# Uncertainty_Device.net
KiCad netlist of a schematic drawn in EAGLE
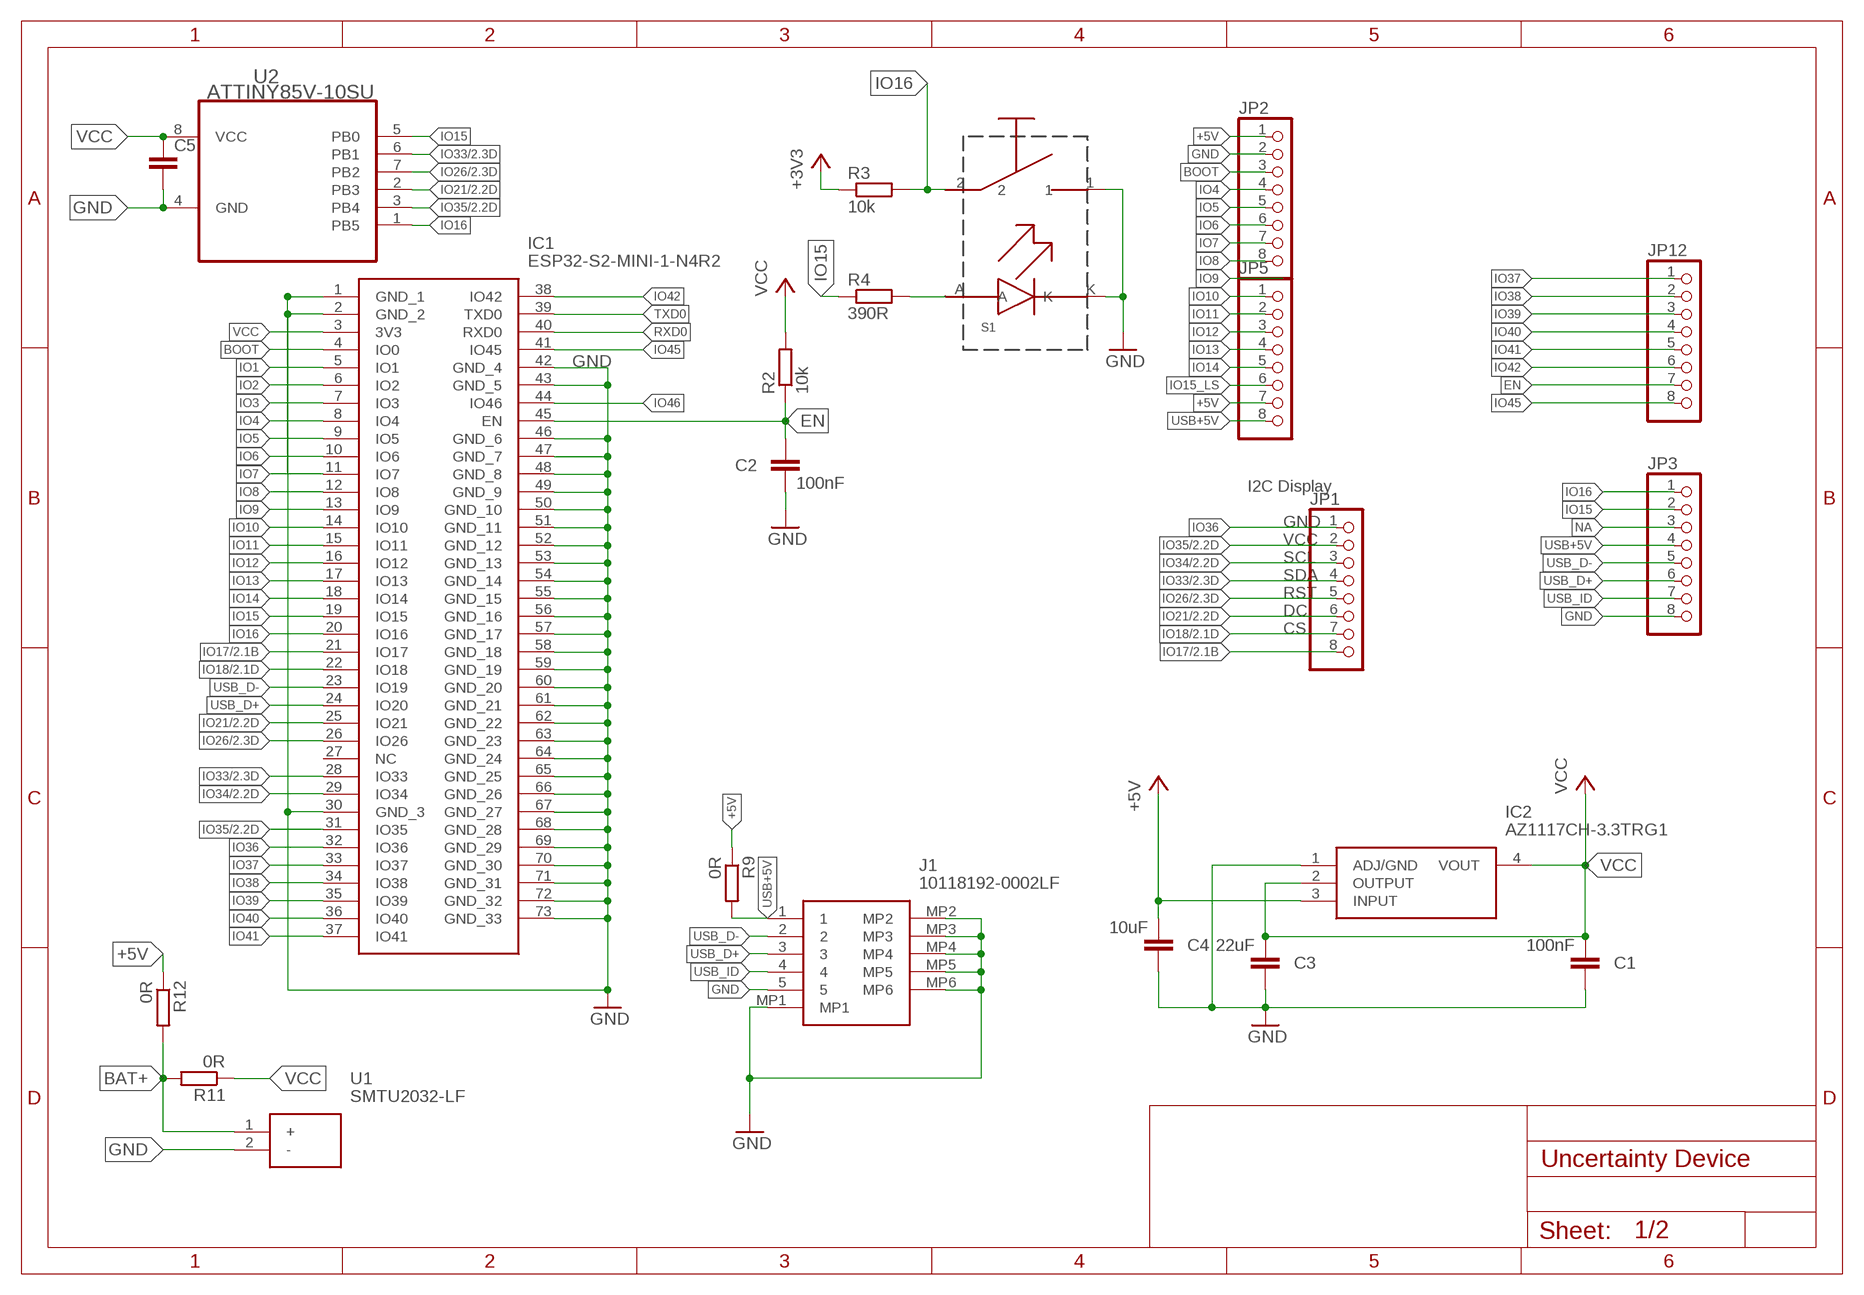
[diagram p0: schematic, sheet 1]
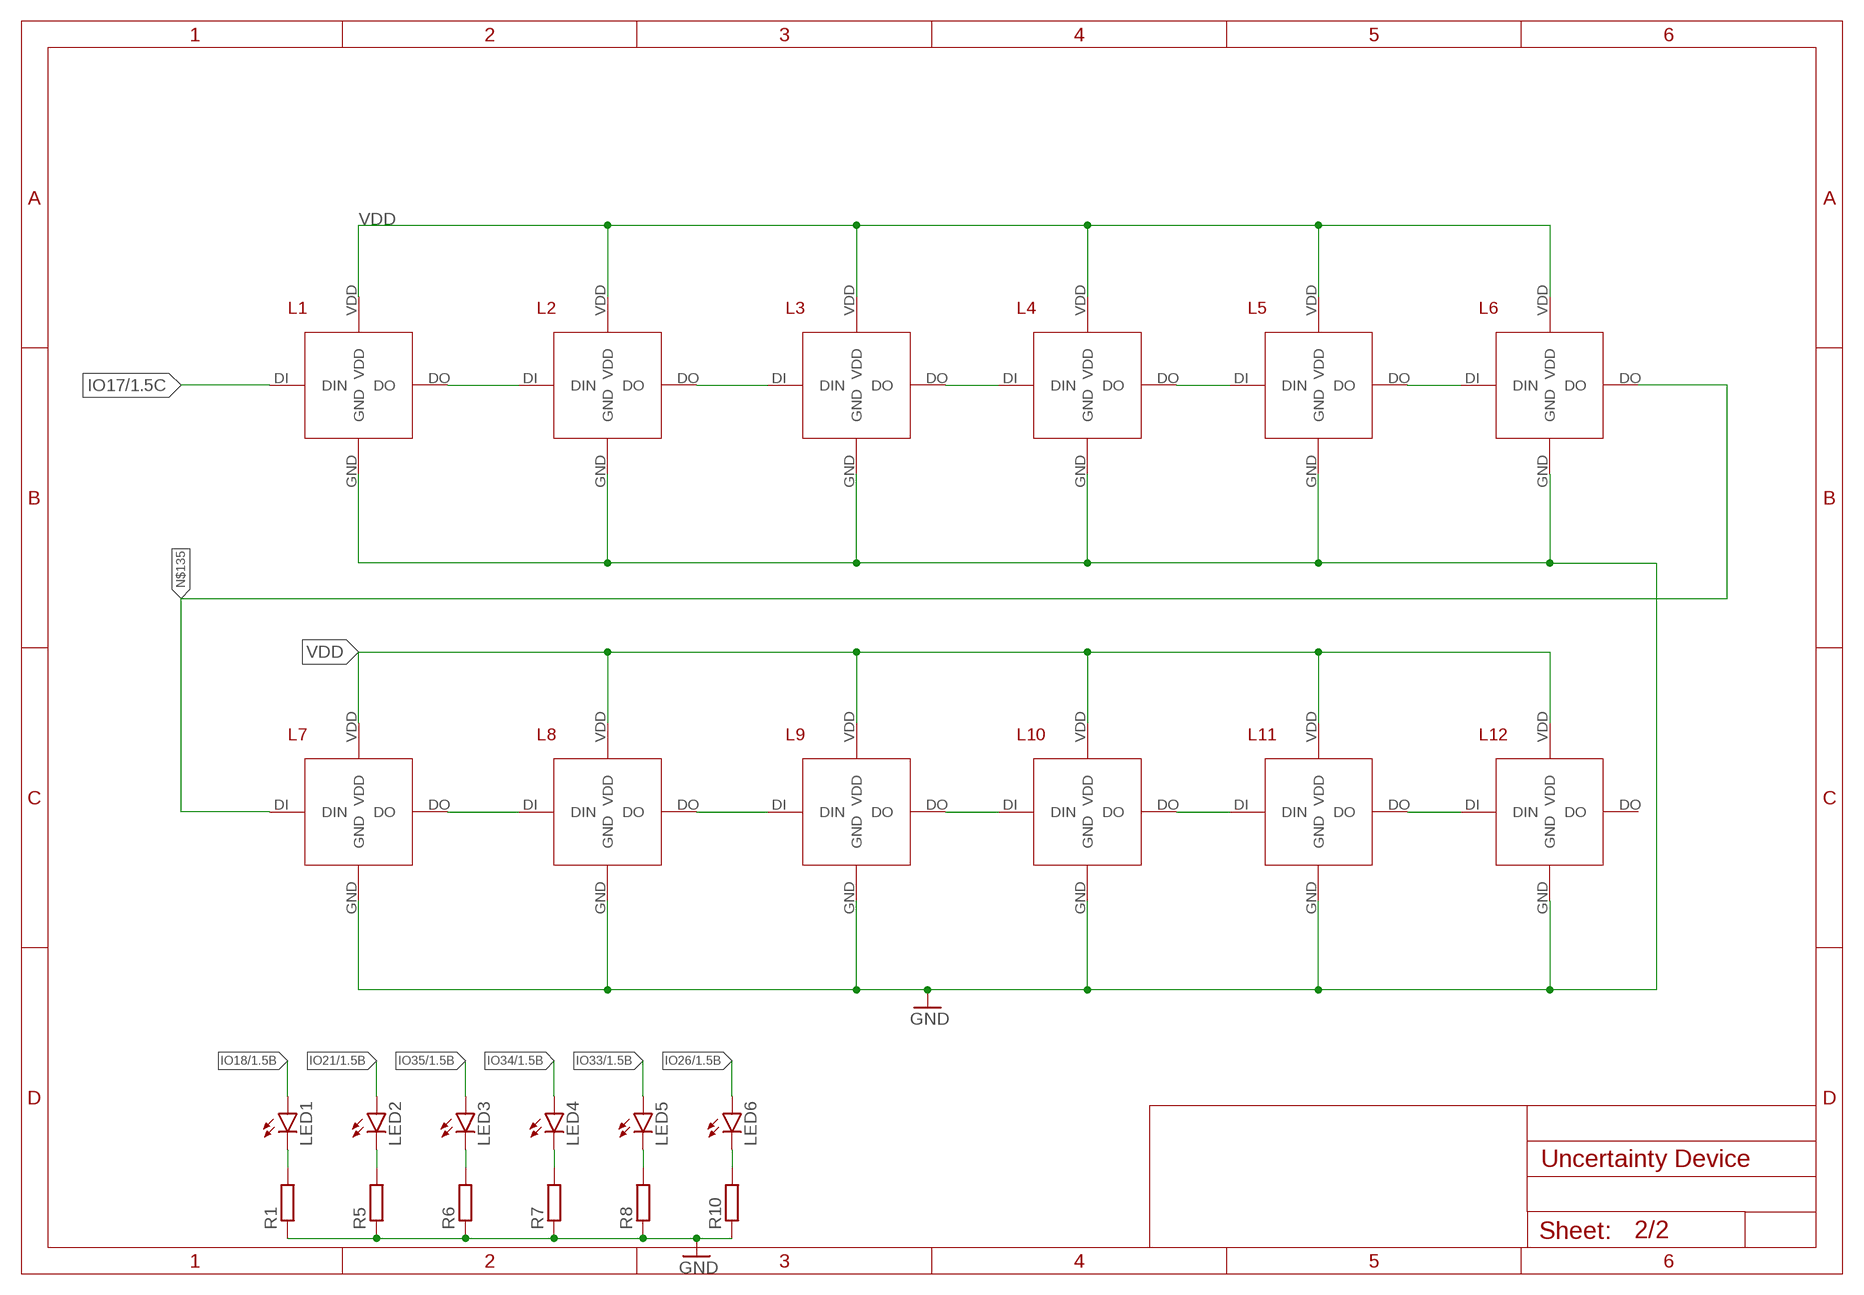
[diagram p1: schematic, sheet 2]

(export (version "E")
  (design (tool "Eeschema 10.0.6"))
  (components
    (comp (ref "C1")
      (value "100nF")
      (footprint "eagle-import:C0805")
      (libsource (lib "eagle-import") (part "C-EUC0805"))
    )
    (comp (ref "C2")
      (value "100nF")
      (footprint "eagle-import:C0805")
      (libsource (lib "eagle-import") (part "C-EUC0805"))
    )
    (comp (ref "C3")
      (value "22uF")
      (footprint "eagle-import:C0805")
      (libsource (lib "eagle-import") (part "C-EUC0805"))
    )
    (comp (ref "C4")
      (value "10uF")
      (footprint "eagle-import:C0805")
      (libsource (lib "eagle-import") (part "C-EUC0805"))
    )
    (comp (ref "C5")
      (value "C-EUC0805")
      (footprint "eagle-import:C0805")
      (libsource (lib "eagle-import") (part "resistor_C-EUC0805"))
    )
    (comp (ref "IC1")
      (value "ESP32-S2-MINI-1-N4R2")
      (footprint "eagle-import:ESP32S2MINI1N4R2")
      (fields (field (name "MOUSER_PART_NUMBER") "356-ESP32S2MINI1N4R2"))
      (libsource (lib "eagle-import") (part "ESP32-S2-MINI-1-N4R2"))
    )
    (comp (ref "IC2")
      (value "AZ1117CH-3.3TRG1")
      (footprint "eagle-import:SOT230P700X180-4N")
      (fields (field (name "MOUSER_PART_NUMBER") "621-AZ1117CH-3.3TRG1"))
      (libsource (lib "eagle-import") (part "AZ1117CH-3.3TRG1"))
    )
    (comp (ref "J1")
      (value "10118192-0002LF")
      (footprint "eagle-import:101181920002LF")
      (libsource (lib "eagle-import") (part "10118192-0002LF"))
    )
    (comp (ref "JP1")
      (value "PINHD-1X8")
      (footprint "eagle-import:1X08")
      (libsource (lib "eagle-import") (part "PINHD-1X8"))
    )
    (comp (ref "JP2")
      (value "PINHD-1X8")
      (footprint "eagle-import:1X08")
      (libsource (lib "eagle-import") (part "PINHD-1X8"))
    )
    (comp (ref "JP3")
      (value "PINHD-1X8")
      (footprint "eagle-import:1X08")
      (libsource (lib "eagle-import") (part "PINHD-1X8"))
    )
    (comp (ref "JP5")
      (value "PINHD-1X8")
      (footprint "eagle-import:1X08")
      (libsource (lib "eagle-import") (part "PINHD-1X8"))
    )
    (comp (ref "JP12")
      (value "PINHD-1X8")
      (footprint "eagle-import:1X08")
      (libsource (lib "eagle-import") (part "PINHD-1X8"))
    )
    (comp (ref "R2")
      (value "10k")
      (footprint "eagle-import:R0805")
      (libsource (lib "eagle-import") (part "R-EU_R0805"))
    )
    (comp (ref "R3")
      (value "10k")
      (footprint "eagle-import:R0805")
      (libsource (lib "eagle-import") (part "R-EU_R0805"))
    )
    (comp (ref "R4")
      (value "390R")
      (footprint "eagle-import:R0805")
      (libsource (lib "eagle-import") (part "R-EU_R0805"))
    )
    (comp (ref "R9")
      (value "0R")
      (footprint "eagle-import:R0805")
      (libsource (lib "eagle-import") (part "R-EU_R0805"))
    )
    (comp (ref "R11")
      (value "0R")
      (footprint "eagle-import:R0805")
      (libsource (lib "eagle-import") (part "R-EU_R0805"))
    )
    (comp (ref "R12")
      (value "0R")
      (footprint "eagle-import:R0805")
      (libsource (lib "eagle-import") (part "R-EU_R0805"))
    )
    (comp (ref "S1")
      (value "3006SMD")
      (footprint "eagle-import:SMD")
      (libsource (lib "eagle-import") (part "3006SMD"))
    )
    (comp (ref "U1")
      (value "SMTU2032-LF")
      (footprint "eagle-import:SMTU2032LF")
      (fields (field (name "MOUSER_PART_NUMBER") "614-SMTU2032-LF"))
      (libsource (lib "eagle-import") (part "SMTU2032-LF"))
    )
    (comp (ref "U2")
      (value "ATTINY85V-10SU")
      (footprint "eagle-import:SOIC127P798X216-8N")
      (libsource (lib "eagle-import") (part "ATTINY85V-10SU"))
    )
    (comp (ref "L1")
      (value "XL-1615RGBC")
      (footprint "eagle-import:XL-1615RGBC-WS2812")
      (libsource (lib "eagle-import") (part "XL-1615RGBC"))
    )
    (comp (ref "L2")
      (value "XL-1615RGBC")
      (footprint "eagle-import:XL-1615RGBC-WS2812")
      (libsource (lib "eagle-import") (part "XL-1615RGBC"))
    )
    (comp (ref "L3")
      (value "XL-1615RGBC")
      (footprint "eagle-import:XL-1615RGBC-WS2812")
      (libsource (lib "eagle-import") (part "XL-1615RGBC"))
    )
    (comp (ref "L4")
      (value "XL-1615RGBC")
      (footprint "eagle-import:XL-1615RGBC-WS2812")
      (libsource (lib "eagle-import") (part "XL-1615RGBC"))
    )
    (comp (ref "L5")
      (value "XL-1615RGBC")
      (footprint "eagle-import:XL-1615RGBC-WS2812")
      (libsource (lib "eagle-import") (part "XL-1615RGBC"))
    )
    (comp (ref "L6")
      (value "XL-1615RGBC")
      (footprint "eagle-import:XL-1615RGBC-WS2812")
      (libsource (lib "eagle-import") (part "XL-1615RGBC"))
    )
    (comp (ref "L7")
      (value "XL-1615RGBC")
      (footprint "eagle-import:XL-1615RGBC-WS2812")
      (libsource (lib "eagle-import") (part "XL-1615RGBC"))
    )
    (comp (ref "L8")
      (value "XL-1615RGBC")
      (footprint "eagle-import:XL-1615RGBC-WS2812")
      (libsource (lib "eagle-import") (part "XL-1615RGBC"))
    )
    (comp (ref "L9")
      (value "XL-1615RGBC")
      (footprint "eagle-import:XL-1615RGBC-WS2812")
      (libsource (lib "eagle-import") (part "XL-1615RGBC"))
    )
    (comp (ref "L10")
      (value "XL-1615RGBC")
      (footprint "eagle-import:XL-1615RGBC-WS2812")
      (libsource (lib "eagle-import") (part "XL-1615RGBC"))
    )
    (comp (ref "L11")
      (value "XL-1615RGBC")
      (footprint "eagle-import:XL-1615RGBC-WS2812")
      (libsource (lib "eagle-import") (part "XL-1615RGBC"))
    )
    (comp (ref "L12")
      (value "XL-1615RGBC")
      (footprint "eagle-import:XL-1615RGBC-WS2812")
      (libsource (lib "eagle-import") (part "XL-1615RGBC"))
    )
    (comp (ref "LED1")
      (value "LEDCHIPLED_0805")
      (footprint "eagle-import:CHIPLED_0805")
      (libsource (lib "eagle-import") (part "LEDCHIPLED_0805"))
    )
    (comp (ref "LED2")
      (value "LEDCHIPLED_0805")
      (footprint "eagle-import:CHIPLED_0805")
      (libsource (lib "eagle-import") (part "LEDCHIPLED_0805"))
    )
    (comp (ref "LED3")
      (value "LEDCHIPLED_0805")
      (footprint "eagle-import:CHIPLED_0805")
      (libsource (lib "eagle-import") (part "LEDCHIPLED_0805"))
    )
    (comp (ref "LED4")
      (value "LEDCHIPLED_0805")
      (footprint "eagle-import:CHIPLED_0805")
      (libsource (lib "eagle-import") (part "LEDCHIPLED_0805"))
    )
    (comp (ref "LED5")
      (value "LEDCHIPLED_0805")
      (footprint "eagle-import:CHIPLED_0805")
      (libsource (lib "eagle-import") (part "LEDCHIPLED_0805"))
    )
    (comp (ref "LED6")
      (value "LEDCHIPLED_0805")
      (footprint "eagle-import:CHIPLED_0805")
      (libsource (lib "eagle-import") (part "LEDCHIPLED_0805"))
    )
    (comp (ref "R1")
      (value "R-EU_R0805")
      (footprint "eagle-import:R0805")
      (libsource (lib "eagle-import") (part "R-EU_R0805"))
    )
    (comp (ref "R5")
      (value "R-EU_R0805")
      (footprint "eagle-import:R0805")
      (libsource (lib "eagle-import") (part "R-EU_R0805"))
    )
    (comp (ref "R6")
      (value "R-EU_R0805")
      (footprint "eagle-import:R0805")
      (libsource (lib "eagle-import") (part "R-EU_R0805"))
    )
    (comp (ref "R7")
      (value "R-EU_R0805")
      (footprint "eagle-import:R0805")
      (libsource (lib "eagle-import") (part "R-EU_R0805"))
    )
    (comp (ref "R8")
      (value "R-EU_R0805")
      (footprint "eagle-import:R0805")
      (libsource (lib "eagle-import") (part "R-EU_R0805"))
    )
    (comp (ref "R10")
      (value "R-EU_R0805")
      (footprint "eagle-import:R0805")
      (libsource (lib "eagle-import") (part "R-EU_R0805"))
    )
  )
  (nets
    (net (code "1") (name "+3V3") (class "Default")
      (node (ref "R3") (pin "1") (pinfunction "1_1") (pintype "passive"))
    )
    (net (code "2") (name "+5V") (class "Default")
      (node (ref "C4") (pin "2") (pinfunction "2_2") (pintype "passive"))
      (node (ref "IC2") (pin "3") (pinfunction "INPUT_3") (pintype "bidirectional"))
      (node (ref "JP2") (pin "1") (pinfunction "1_1") (pintype "passive"))
      (node (ref "JP5") (pin "7") (pinfunction "7_7") (pintype "passive"))
      (node (ref "R12") (pin "1") (pinfunction "1_1") (pintype "passive"))
      (node (ref "R9") (pin "1") (pinfunction "1_1") (pintype "passive"))
    )
    (net (code "3") (name "BAT+") (class "Default")
      (node (ref "R11") (pin "2") (pinfunction "2_2") (pintype "passive"))
      (node (ref "R12") (pin "2") (pinfunction "2_2") (pintype "passive"))
      (node (ref "U1") (pin "1") (pinfunction "+_1") (pintype "bidirectional"))
    )
    (net (code "4") (name "BOOT") (class "Default")
      (node (ref "IC1") (pin "4") (pinfunction "IO0_4") (pintype "bidirectional"))
      (node (ref "JP2") (pin "3") (pinfunction "3_3") (pintype "passive"))
    )
    (net (code "5") (name "EN") (class "Default")
      (node (ref "C2") (pin "1") (pinfunction "1_1") (pintype "passive"))
      (node (ref "IC1") (pin "45") (pinfunction "EN_45") (pintype "bidirectional"))
      (node (ref "JP12") (pin "7") (pinfunction "7_7") (pintype "passive"))
      (node (ref "R2") (pin "1") (pinfunction "1_1") (pintype "passive"))
    )
    (net (code "6") (name "GND") (class "Default")
      (node (ref "C1") (pin "1") (pinfunction "1_1") (pintype "passive"))
      (node (ref "C2") (pin "2") (pinfunction "2_2") (pintype "passive"))
      (node (ref "C3") (pin "1") (pinfunction "1_1") (pintype "passive"))
      (node (ref "C4") (pin "1") (pinfunction "1_1") (pintype "passive"))
      (node (ref "C5") (pin "2") (pinfunction "2_2") (pintype "passive"))
      (node (ref "IC1") (pin "1") (pinfunction "GND_1_1") (pintype "bidirectional"))
      (node (ref "IC1") (pin "2") (pinfunction "GND_2_2") (pintype "bidirectional"))
      (node (ref "IC1") (pin "30") (pinfunction "GND_3_30") (pintype "bidirectional"))
      (node (ref "IC1") (pin "42") (pinfunction "GND_4_42") (pintype "bidirectional"))
      (node (ref "IC1") (pin "43") (pinfunction "GND_5_43") (pintype "bidirectional"))
      (node (ref "IC1") (pin "46") (pinfunction "GND_6_46") (pintype "bidirectional"))
      (node (ref "IC1") (pin "47") (pinfunction "GND_7_47") (pintype "bidirectional"))
      (node (ref "IC1") (pin "48") (pinfunction "GND_8_48") (pintype "bidirectional"))
      (node (ref "IC1") (pin "49") (pinfunction "GND_9_49") (pintype "bidirectional"))
      (node (ref "IC1") (pin "50") (pinfunction "GND_10_50") (pintype "bidirectional"))
      (node (ref "IC1") (pin "51") (pinfunction "GND_11_51") (pintype "bidirectional"))
      (node (ref "IC1") (pin "52") (pinfunction "GND_12_52") (pintype "bidirectional"))
      (node (ref "IC1") (pin "53") (pinfunction "GND_13_53") (pintype "bidirectional"))
      (node (ref "IC1") (pin "54") (pinfunction "GND_14_54") (pintype "bidirectional"))
      (node (ref "IC1") (pin "55") (pinfunction "GND_15_55") (pintype "bidirectional"))
      (node (ref "IC1") (pin "56") (pinfunction "GND_16_56") (pintype "bidirectional"))
      (node (ref "IC1") (pin "57") (pinfunction "GND_17_57") (pintype "bidirectional"))
      (node (ref "IC1") (pin "58") (pinfunction "GND_18_58") (pintype "bidirectional"))
      (node (ref "IC1") (pin "59") (pinfunction "GND_19_59") (pintype "bidirectional"))
      (node (ref "IC1") (pin "60") (pinfunction "GND_20_60") (pintype "bidirectional"))
      (node (ref "IC1") (pin "61") (pinfunction "GND_21_61") (pintype "bidirectional"))
      (node (ref "IC1") (pin "62") (pinfunction "GND_22_62") (pintype "bidirectional"))
      (node (ref "IC1") (pin "63") (pinfunction "GND_23_63") (pintype "bidirectional"))
      (node (ref "IC1") (pin "64") (pinfunction "GND_24_64") (pintype "bidirectional"))
      (node (ref "IC1") (pin "65") (pinfunction "GND_25_65") (pintype "bidirectional"))
      (node (ref "IC1") (pin "66") (pinfunction "GND_26_66") (pintype "bidirectional"))
      (node (ref "IC1") (pin "67") (pinfunction "GND_27_67") (pintype "bidirectional"))
      (node (ref "IC1") (pin "68") (pinfunction "GND_28_68") (pintype "bidirectional"))
      (node (ref "IC1") (pin "69") (pinfunction "GND_29_69") (pintype "bidirectional"))
      (node (ref "IC1") (pin "70") (pinfunction "GND_30_70") (pintype "bidirectional"))
      (node (ref "IC1") (pin "71") (pinfunction "GND_31_71") (pintype "bidirectional"))
      (node (ref "IC1") (pin "72") (pinfunction "GND_32_72") (pintype "bidirectional"))
      (node (ref "IC1") (pin "73") (pinfunction "GND_33_73") (pintype "bidirectional"))
      (node (ref "IC2") (pin "1") (pinfunction "ADJ/GND_1") (pintype "bidirectional"))
      (node (ref "J1") (pin "5") (pinfunction "5_5") (pintype "bidirectional"))
      (node (ref "J1") (pin "MP1") (pinfunction "MP1_MP1") (pintype "bidirectional"))
      (node (ref "J1") (pin "MP2") (pinfunction "MP2_MP2") (pintype "bidirectional"))
      (node (ref "J1") (pin "MP3") (pinfunction "MP3_MP3") (pintype "bidirectional"))
      (node (ref "J1") (pin "MP4") (pinfunction "MP4_MP4") (pintype "bidirectional"))
      (node (ref "J1") (pin "MP5") (pinfunction "MP5_MP5") (pintype "bidirectional"))
      (node (ref "J1") (pin "MP6") (pinfunction "MP6_MP6") (pintype "bidirectional"))
      (node (ref "JP2") (pin "2") (pinfunction "2_2") (pintype "passive"))
      (node (ref "JP3") (pin "8") (pinfunction "8_8") (pintype "passive"))
      (node (ref "L1") (pin "GND") (pinfunction "GND_GND") (pintype "bidirectional"))
      (node (ref "L10") (pin "GND") (pinfunction "GND_GND") (pintype "bidirectional"))
      (node (ref "L11") (pin "GND") (pinfunction "GND_GND") (pintype "bidirectional"))
      (node (ref "L12") (pin "GND") (pinfunction "GND_GND") (pintype "bidirectional"))
      (node (ref "L2") (pin "GND") (pinfunction "GND_GND") (pintype "bidirectional"))
      (node (ref "L3") (pin "GND") (pinfunction "GND_GND") (pintype "bidirectional"))
      (node (ref "L4") (pin "GND") (pinfunction "GND_GND") (pintype "bidirectional"))
      (node (ref "L5") (pin "GND") (pinfunction "GND_GND") (pintype "bidirectional"))
      (node (ref "L6") (pin "GND") (pinfunction "GND_GND") (pintype "bidirectional"))
      (node (ref "L7") (pin "GND") (pinfunction "GND_GND") (pintype "bidirectional"))
      (node (ref "L8") (pin "GND") (pinfunction "GND_GND") (pintype "bidirectional"))
      (node (ref "L9") (pin "GND") (pinfunction "GND_GND") (pintype "bidirectional"))
      (node (ref "R1") (pin "1") (pinfunction "1_1") (pintype "passive"))
      (node (ref "R10") (pin "1") (pinfunction "1_1") (pintype "passive"))
      (node (ref "R5") (pin "1") (pinfunction "1_1") (pintype "passive"))
      (node (ref "R6") (pin "1") (pinfunction "1_1") (pintype "passive"))
      (node (ref "R7") (pin "1") (pinfunction "1_1") (pintype "passive"))
      (node (ref "R8") (pin "1") (pinfunction "1_1") (pintype "passive"))
      (node (ref "S1") (pin "1") (pinfunction "1_1") (pintype "bidirectional"))
      (node (ref "S1") (pin "K") (pinfunction "K_K") (pintype "bidirectional"))
      (node (ref "U1") (pin "2") (pinfunction "-_2") (pintype "bidirectional"))
      (node (ref "U2") (pin "4") (pinfunction "GND_4") (pintype "passive"))
    )
    (net (code "7") (name "IO1") (class "Default")
      (node (ref "IC1") (pin "5") (pinfunction "IO1_5") (pintype "bidirectional"))
    )
    (net (code "8") (name "IO2") (class "Default")
      (node (ref "IC1") (pin "6") (pinfunction "IO2_6") (pintype "bidirectional"))
    )
    (net (code "9") (name "IO3") (class "Default")
      (node (ref "IC1") (pin "7") (pinfunction "IO3_7") (pintype "bidirectional"))
    )
    (net (code "10") (name "IO4") (class "Default")
      (node (ref "IC1") (pin "8") (pinfunction "IO4_8") (pintype "bidirectional"))
      (node (ref "JP2") (pin "4") (pinfunction "4_4") (pintype "passive"))
    )
    (net (code "11") (name "IO5") (class "Default")
      (node (ref "IC1") (pin "9") (pinfunction "IO5_9") (pintype "bidirectional"))
      (node (ref "JP2") (pin "5") (pinfunction "5_5") (pintype "passive"))
    )
    (net (code "12") (name "IO6") (class "Default")
      (node (ref "IC1") (pin "10") (pinfunction "IO6_10") (pintype "bidirectional"))
      (node (ref "JP2") (pin "6") (pinfunction "6_6") (pintype "passive"))
    )
    (net (code "13") (name "IO7") (class "Default")
      (node (ref "IC1") (pin "11") (pinfunction "IO7_11") (pintype "bidirectional"))
      (node (ref "JP2") (pin "7") (pinfunction "7_7") (pintype "passive"))
    )
    (net (code "14") (name "IO8") (class "Default")
      (node (ref "IC1") (pin "12") (pinfunction "IO8_12") (pintype "bidirectional"))
      (node (ref "JP2") (pin "8") (pinfunction "8_8") (pintype "passive"))
    )
    (net (code "15") (name "IO9") (class "Default")
      (node (ref "IC1") (pin "13") (pinfunction "IO9_13") (pintype "bidirectional"))
    )
    (net (code "16") (name "IO10") (class "Default")
      (node (ref "IC1") (pin "14") (pinfunction "IO10_14") (pintype "bidirectional"))
      (node (ref "JP5") (pin "1") (pinfunction "1_1") (pintype "passive"))
    )
    (net (code "17") (name "IO11") (class "Default")
      (node (ref "IC1") (pin "15") (pinfunction "IO11_15") (pintype "bidirectional"))
      (node (ref "JP5") (pin "2") (pinfunction "2_2") (pintype "passive"))
    )
    (net (code "18") (name "IO12") (class "Default")
      (node (ref "IC1") (pin "16") (pinfunction "IO12_16") (pintype "bidirectional"))
      (node (ref "JP5") (pin "3") (pinfunction "3_3") (pintype "passive"))
    )
    (net (code "19") (name "IO13") (class "Default")
      (node (ref "IC1") (pin "17") (pinfunction "IO13_17") (pintype "bidirectional"))
      (node (ref "JP5") (pin "4") (pinfunction "4_4") (pintype "passive"))
    )
    (net (code "20") (name "IO14") (class "Default")
      (node (ref "IC1") (pin "18") (pinfunction "IO14_18") (pintype "bidirectional"))
      (node (ref "JP5") (pin "5") (pinfunction "5_5") (pintype "passive"))
    )
    (net (code "21") (name "IO15") (class "Default")
      (node (ref "IC1") (pin "19") (pinfunction "IO15_19") (pintype "bidirectional"))
      (node (ref "JP3") (pin "2") (pinfunction "2_2") (pintype "passive"))
      (node (ref "R4") (pin "1") (pinfunction "1_1") (pintype "passive"))
      (node (ref "U2") (pin "5") (pinfunction "PB0_5") (pintype "bidirectional"))
    )
    (net (code "22") (name "IO15_LS") (class "Default")
      (node (ref "JP5") (pin "6") (pinfunction "6_6") (pintype "passive"))
    )
    (net (code "23") (name "IO16") (class "Default")
      (node (ref "IC1") (pin "20") (pinfunction "IO16_20") (pintype "bidirectional"))
      (node (ref "JP3") (pin "1") (pinfunction "1_1") (pintype "passive"))
      (node (ref "R3") (pin "2") (pinfunction "2_2") (pintype "passive"))
      (node (ref "S1") (pin "2") (pinfunction "2_2") (pintype "bidirectional"))
      (node (ref "U2") (pin "1") (pinfunction "PB5_1") (pintype "bidirectional"))
    )
    (net (code "24") (name "IO17") (class "Default")
      (node (ref "IC1") (pin "21") (pinfunction "IO17_21") (pintype "bidirectional"))
      (node (ref "JP1") (pin "8") (pinfunction "8_8") (pintype "passive"))
      (node (ref "L1") (pin "DI") (pinfunction "DIN_DI") (pintype "bidirectional"))
    )
    (net (code "25") (name "IO18") (class "Default")
      (node (ref "IC1") (pin "22") (pinfunction "IO18_22") (pintype "bidirectional"))
      (node (ref "JP1") (pin "7") (pinfunction "7_7") (pintype "passive"))
      (node (ref "LED1") (pin "A") (pinfunction "A_A") (pintype "passive"))
    )
    (net (code "26") (name "IO21") (class "Default")
      (node (ref "IC1") (pin "25") (pinfunction "IO21_25") (pintype "bidirectional"))
      (node (ref "JP1") (pin "6") (pinfunction "6_6") (pintype "passive"))
      (node (ref "LED2") (pin "A") (pinfunction "A_A") (pintype "passive"))
      (node (ref "U2") (pin "2") (pinfunction "PB3_2") (pintype "bidirectional"))
    )
    (net (code "27") (name "IO26") (class "Default")
      (node (ref "IC1") (pin "26") (pinfunction "IO26_26") (pintype "bidirectional"))
      (node (ref "JP1") (pin "5") (pinfunction "5_5") (pintype "passive"))
      (node (ref "LED6") (pin "A") (pinfunction "A_A") (pintype "passive"))
      (node (ref "U2") (pin "7") (pinfunction "PB2_7") (pintype "bidirectional"))
    )
    (net (code "28") (name "IO33") (class "Default")
      (node (ref "IC1") (pin "28") (pinfunction "IO33_28") (pintype "bidirectional"))
      (node (ref "JP1") (pin "4") (pinfunction "4_4") (pintype "passive"))
      (node (ref "LED5") (pin "A") (pinfunction "A_A") (pintype "passive"))
      (node (ref "U2") (pin "6") (pinfunction "PB1_6") (pintype "bidirectional"))
    )
    (net (code "29") (name "IO34") (class "Default")
      (node (ref "IC1") (pin "29") (pinfunction "IO34_29") (pintype "bidirectional"))
      (node (ref "JP1") (pin "3") (pinfunction "3_3") (pintype "passive"))
      (node (ref "LED4") (pin "A") (pinfunction "A_A") (pintype "passive"))
    )
    (net (code "30") (name "IO35") (class "Default")
      (node (ref "IC1") (pin "31") (pinfunction "IO35_31") (pintype "bidirectional"))
      (node (ref "JP1") (pin "2") (pinfunction "2_2") (pintype "passive"))
      (node (ref "LED3") (pin "A") (pinfunction "A_A") (pintype "passive"))
      (node (ref "U2") (pin "3") (pinfunction "PB4_3") (pintype "bidirectional"))
    )
    (net (code "31") (name "IO36") (class "Default")
      (node (ref "IC1") (pin "32") (pinfunction "IO36_32") (pintype "bidirectional"))
      (node (ref "JP1") (pin "1") (pinfunction "1_1") (pintype "passive"))
    )
    (net (code "32") (name "IO37") (class "Default")
      (node (ref "IC1") (pin "33") (pinfunction "IO37_33") (pintype "bidirectional"))
      (node (ref "JP12") (pin "1") (pinfunction "1_1") (pintype "passive"))
    )
    (net (code "33") (name "IO38") (class "Default")
      (node (ref "IC1") (pin "34") (pinfunction "IO38_34") (pintype "bidirectional"))
      (node (ref "JP12") (pin "2") (pinfunction "2_2") (pintype "passive"))
    )
    (net (code "34") (name "IO39") (class "Default")
      (node (ref "IC1") (pin "35") (pinfunction "IO39_35") (pintype "bidirectional"))
      (node (ref "JP12") (pin "3") (pinfunction "3_3") (pintype "passive"))
    )
    (net (code "35") (name "IO40") (class "Default")
      (node (ref "IC1") (pin "36") (pinfunction "IO40_36") (pintype "bidirectional"))
      (node (ref "JP12") (pin "4") (pinfunction "4_4") (pintype "passive"))
    )
    (net (code "36") (name "IO41") (class "Default")
      (node (ref "IC1") (pin "37") (pinfunction "IO41_37") (pintype "bidirectional"))
      (node (ref "JP12") (pin "5") (pinfunction "5_5") (pintype "passive"))
    )
    (net (code "37") (name "IO42") (class "Default")
      (node (ref "IC1") (pin "38") (pinfunction "IO42_38") (pintype "bidirectional"))
      (node (ref "JP12") (pin "6") (pinfunction "6_6") (pintype "passive"))
    )
    (net (code "38") (name "IO45") (class "Default")
      (node (ref "IC1") (pin "41") (pinfunction "IO45_41") (pintype "bidirectional"))
      (node (ref "JP12") (pin "8") (pinfunction "8_8") (pintype "passive"))
    )
    (net (code "39") (name "IO46") (class "Default")
      (node (ref "IC1") (pin "44") (pinfunction "IO46_44") (pintype "bidirectional"))
    )
    (net (code "40") (name "N$135") (class "Default")
      (node (ref "L6") (pin "DO") (pinfunction "DO_DO") (pintype "bidirectional"))
      (node (ref "L7") (pin "DI") (pinfunction "DIN_DI") (pintype "bidirectional"))
    )
    (net (code "41") (name "NA") (class "Default")
      (node (ref "JP3") (pin "3") (pinfunction "3_3") (pintype "passive"))
    )
    (net (code "42") (name "Net-(L2-DIN)") (class "Default")
      (node (ref "L1") (pin "DO") (pinfunction "DO_DO") (pintype "bidirectional"))
      (node (ref "L2") (pin "DI") (pinfunction "DIN_DI") (pintype "bidirectional"))
    )
    (net (code "43") (name "Net-(L3-DIN)") (class "Default")
      (node (ref "L2") (pin "DO") (pinfunction "DO_DO") (pintype "bidirectional"))
      (node (ref "L3") (pin "DI") (pinfunction "DIN_DI") (pintype "bidirectional"))
    )
    (net (code "44") (name "Net-(L4-DIN)") (class "Default")
      (node (ref "L3") (pin "DO") (pinfunction "DO_DO") (pintype "bidirectional"))
      (node (ref "L4") (pin "DI") (pinfunction "DIN_DI") (pintype "bidirectional"))
    )
    (net (code "45") (name "Net-(L5-DIN)") (class "Default")
      (node (ref "L4") (pin "DO") (pinfunction "DO_DO") (pintype "bidirectional"))
      (node (ref "L5") (pin "DI") (pinfunction "DIN_DI") (pintype "bidirectional"))
    )
    (net (code "46") (name "Net-(L6-DIN)") (class "Default")
      (node (ref "L5") (pin "DO") (pinfunction "DO_DO") (pintype "bidirectional"))
      (node (ref "L6") (pin "DI") (pinfunction "DIN_DI") (pintype "bidirectional"))
    )
    (net (code "47") (name "Net-(L8-DIN)") (class "Default")
      (node (ref "L7") (pin "DO") (pinfunction "DO_DO") (pintype "bidirectional"))
      (node (ref "L8") (pin "DI") (pinfunction "DIN_DI") (pintype "bidirectional"))
    )
    (net (code "48") (name "Net-(L9-DIN)") (class "Default")
      (node (ref "L8") (pin "DO") (pinfunction "DO_DO") (pintype "bidirectional"))
      (node (ref "L9") (pin "DI") (pinfunction "DIN_DI") (pintype "bidirectional"))
    )
    (net (code "49") (name "Net-(L10-DIN)") (class "Default")
      (node (ref "L10") (pin "DI") (pinfunction "DIN_DI") (pintype "bidirectional"))
      (node (ref "L9") (pin "DO") (pinfunction "DO_DO") (pintype "bidirectional"))
    )
    (net (code "50") (name "Net-(L11-DIN)") (class "Default")
      (node (ref "L10") (pin "DO") (pinfunction "DO_DO") (pintype "bidirectional"))
      (node (ref "L11") (pin "DI") (pinfunction "DIN_DI") (pintype "bidirectional"))
    )
    (net (code "51") (name "Net-(L12-DIN)") (class "Default")
      (node (ref "L11") (pin "DO") (pinfunction "DO_DO") (pintype "bidirectional"))
      (node (ref "L12") (pin "DI") (pinfunction "DIN_DI") (pintype "bidirectional"))
    )
    (net (code "52") (name "Net-(LED1-PadC)") (class "Default")
      (node (ref "LED1") (pin "C") (pinfunction "C_C") (pintype "passive"))
      (node (ref "R1") (pin "2") (pinfunction "2_2") (pintype "passive"))
    )
    (net (code "53") (name "Net-(LED2-PadC)") (class "Default")
      (node (ref "LED2") (pin "C") (pinfunction "C_C") (pintype "passive"))
      (node (ref "R5") (pin "2") (pinfunction "2_2") (pintype "passive"))
    )
    (net (code "54") (name "Net-(LED3-PadC)") (class "Default")
      (node (ref "LED3") (pin "C") (pinfunction "C_C") (pintype "passive"))
      (node (ref "R6") (pin "2") (pinfunction "2_2") (pintype "passive"))
    )
    (net (code "55") (name "Net-(LED4-PadC)") (class "Default")
      (node (ref "LED4") (pin "C") (pinfunction "C_C") (pintype "passive"))
      (node (ref "R7") (pin "2") (pinfunction "2_2") (pintype "passive"))
    )
    (net (code "56") (name "Net-(LED5-PadC)") (class "Default")
      (node (ref "LED5") (pin "C") (pinfunction "C_C") (pintype "passive"))
      (node (ref "R8") (pin "2") (pinfunction "2_2") (pintype "passive"))
    )
    (net (code "57") (name "Net-(LED6-PadC)") (class "Default")
      (node (ref "LED6") (pin "C") (pinfunction "C_C") (pintype "passive"))
      (node (ref "R10") (pin "2") (pinfunction "2_2") (pintype "passive"))
    )
    (net (code "58") (name "Net-(R4-Pad2)") (class "Default")
      (node (ref "R4") (pin "2") (pinfunction "2_2") (pintype "passive"))
      (node (ref "S1") (pin "A") (pinfunction "A_A") (pintype "bidirectional"))
    )
    (net (code "59") (name "RXD0") (class "Default")
      (node (ref "IC1") (pin "40") (pinfunction "RXD0_40") (pintype "bidirectional"))
    )
    (net (code "60") (name "TXD0") (class "Default")
      (node (ref "IC1") (pin "39") (pinfunction "TXD0_39") (pintype "bidirectional"))
    )
    (net (code "61") (name "USB+5V") (class "Default")
      (node (ref "J1") (pin "1") (pinfunction "1_1") (pintype "bidirectional"))
      (node (ref "JP3") (pin "4") (pinfunction "4_4") (pintype "passive"))
      (node (ref "JP5") (pin "8") (pinfunction "8_8") (pintype "passive"))
      (node (ref "R9") (pin "2") (pinfunction "2_2") (pintype "passive"))
    )
    (net (code "62") (name "USB_D+") (class "Default")
      (node (ref "IC1") (pin "24") (pinfunction "IO20_24") (pintype "bidirectional"))
      (node (ref "J1") (pin "3") (pinfunction "3_3") (pintype "bidirectional"))
      (node (ref "JP3") (pin "6") (pinfunction "6_6") (pintype "passive"))
    )
    (net (code "63") (name "USB_D-") (class "Default")
      (node (ref "IC1") (pin "23") (pinfunction "IO19_23") (pintype "bidirectional"))
      (node (ref "J1") (pin "2") (pinfunction "2_2") (pintype "bidirectional"))
      (node (ref "JP3") (pin "5") (pinfunction "5_5") (pintype "passive"))
    )
    (net (code "64") (name "USB_ID") (class "Default")
      (node (ref "J1") (pin "4") (pinfunction "4_4") (pintype "bidirectional"))
      (node (ref "JP3") (pin "7") (pinfunction "7_7") (pintype "passive"))
    )
    (net (code "65") (name "VCC") (class "Default")
      (node (ref "C1") (pin "2") (pinfunction "2_2") (pintype "passive"))
      (node (ref "C3") (pin "2") (pinfunction "2_2") (pintype "passive"))
      (node (ref "C5") (pin "1") (pinfunction "1_1") (pintype "passive"))
      (node (ref "IC1") (pin "3") (pinfunction "3V3_3") (pintype "bidirectional"))
      (node (ref "IC2") (pin "2") (pinfunction "OUTPUT_2") (pintype "bidirectional"))
      (node (ref "IC2") (pin "4") (pinfunction "VOUT_4") (pintype "bidirectional"))
      (node (ref "R11") (pin "1") (pinfunction "1_1") (pintype "passive"))
      (node (ref "R2") (pin "2") (pinfunction "2_2") (pintype "passive"))
      (node (ref "U2") (pin "8") (pinfunction "VCC_8") (pintype "power_in"))
    )
    (net (code "66") (name "VDD") (class "Default")
      (node (ref "L1") (pin "VDD") (pinfunction "VDD_VDD") (pintype "bidirectional"))
      (node (ref "L10") (pin "VDD") (pinfunction "VDD_VDD") (pintype "bidirectional"))
      (node (ref "L11") (pin "VDD") (pinfunction "VDD_VDD") (pintype "bidirectional"))
      (node (ref "L12") (pin "VDD") (pinfunction "VDD_VDD") (pintype "bidirectional"))
      (node (ref "L2") (pin "VDD") (pinfunction "VDD_VDD") (pintype "bidirectional"))
      (node (ref "L3") (pin "VDD") (pinfunction "VDD_VDD") (pintype "bidirectional"))
      (node (ref "L4") (pin "VDD") (pinfunction "VDD_VDD") (pintype "bidirectional"))
      (node (ref "L5") (pin "VDD") (pinfunction "VDD_VDD") (pintype "bidirectional"))
      (node (ref "L6") (pin "VDD") (pinfunction "VDD_VDD") (pintype "bidirectional"))
      (node (ref "L7") (pin "VDD") (pinfunction "VDD_VDD") (pintype "bidirectional"))
      (node (ref "L8") (pin "VDD") (pinfunction "VDD_VDD") (pintype "bidirectional"))
      (node (ref "L9") (pin "VDD") (pinfunction "VDD_VDD") (pintype "bidirectional"))
    )
    (net (code "67") (name "unconnected-(IC1-NC-Pad27)") (class "Default")
      (node (ref "IC1") (pin "27") (pinfunction "NC_27") (pintype "no_connect"))
    )
    (net (code "68") (name "unconnected-(L12-PadDO)") (class "Default")
      (node (ref "L12") (pin "DO") (pinfunction "DO_DO") (pintype "bidirectional"))
    )
  )
)
